# F401.net
KiCad netlist of a schematic drawn in EasyEDA Pro
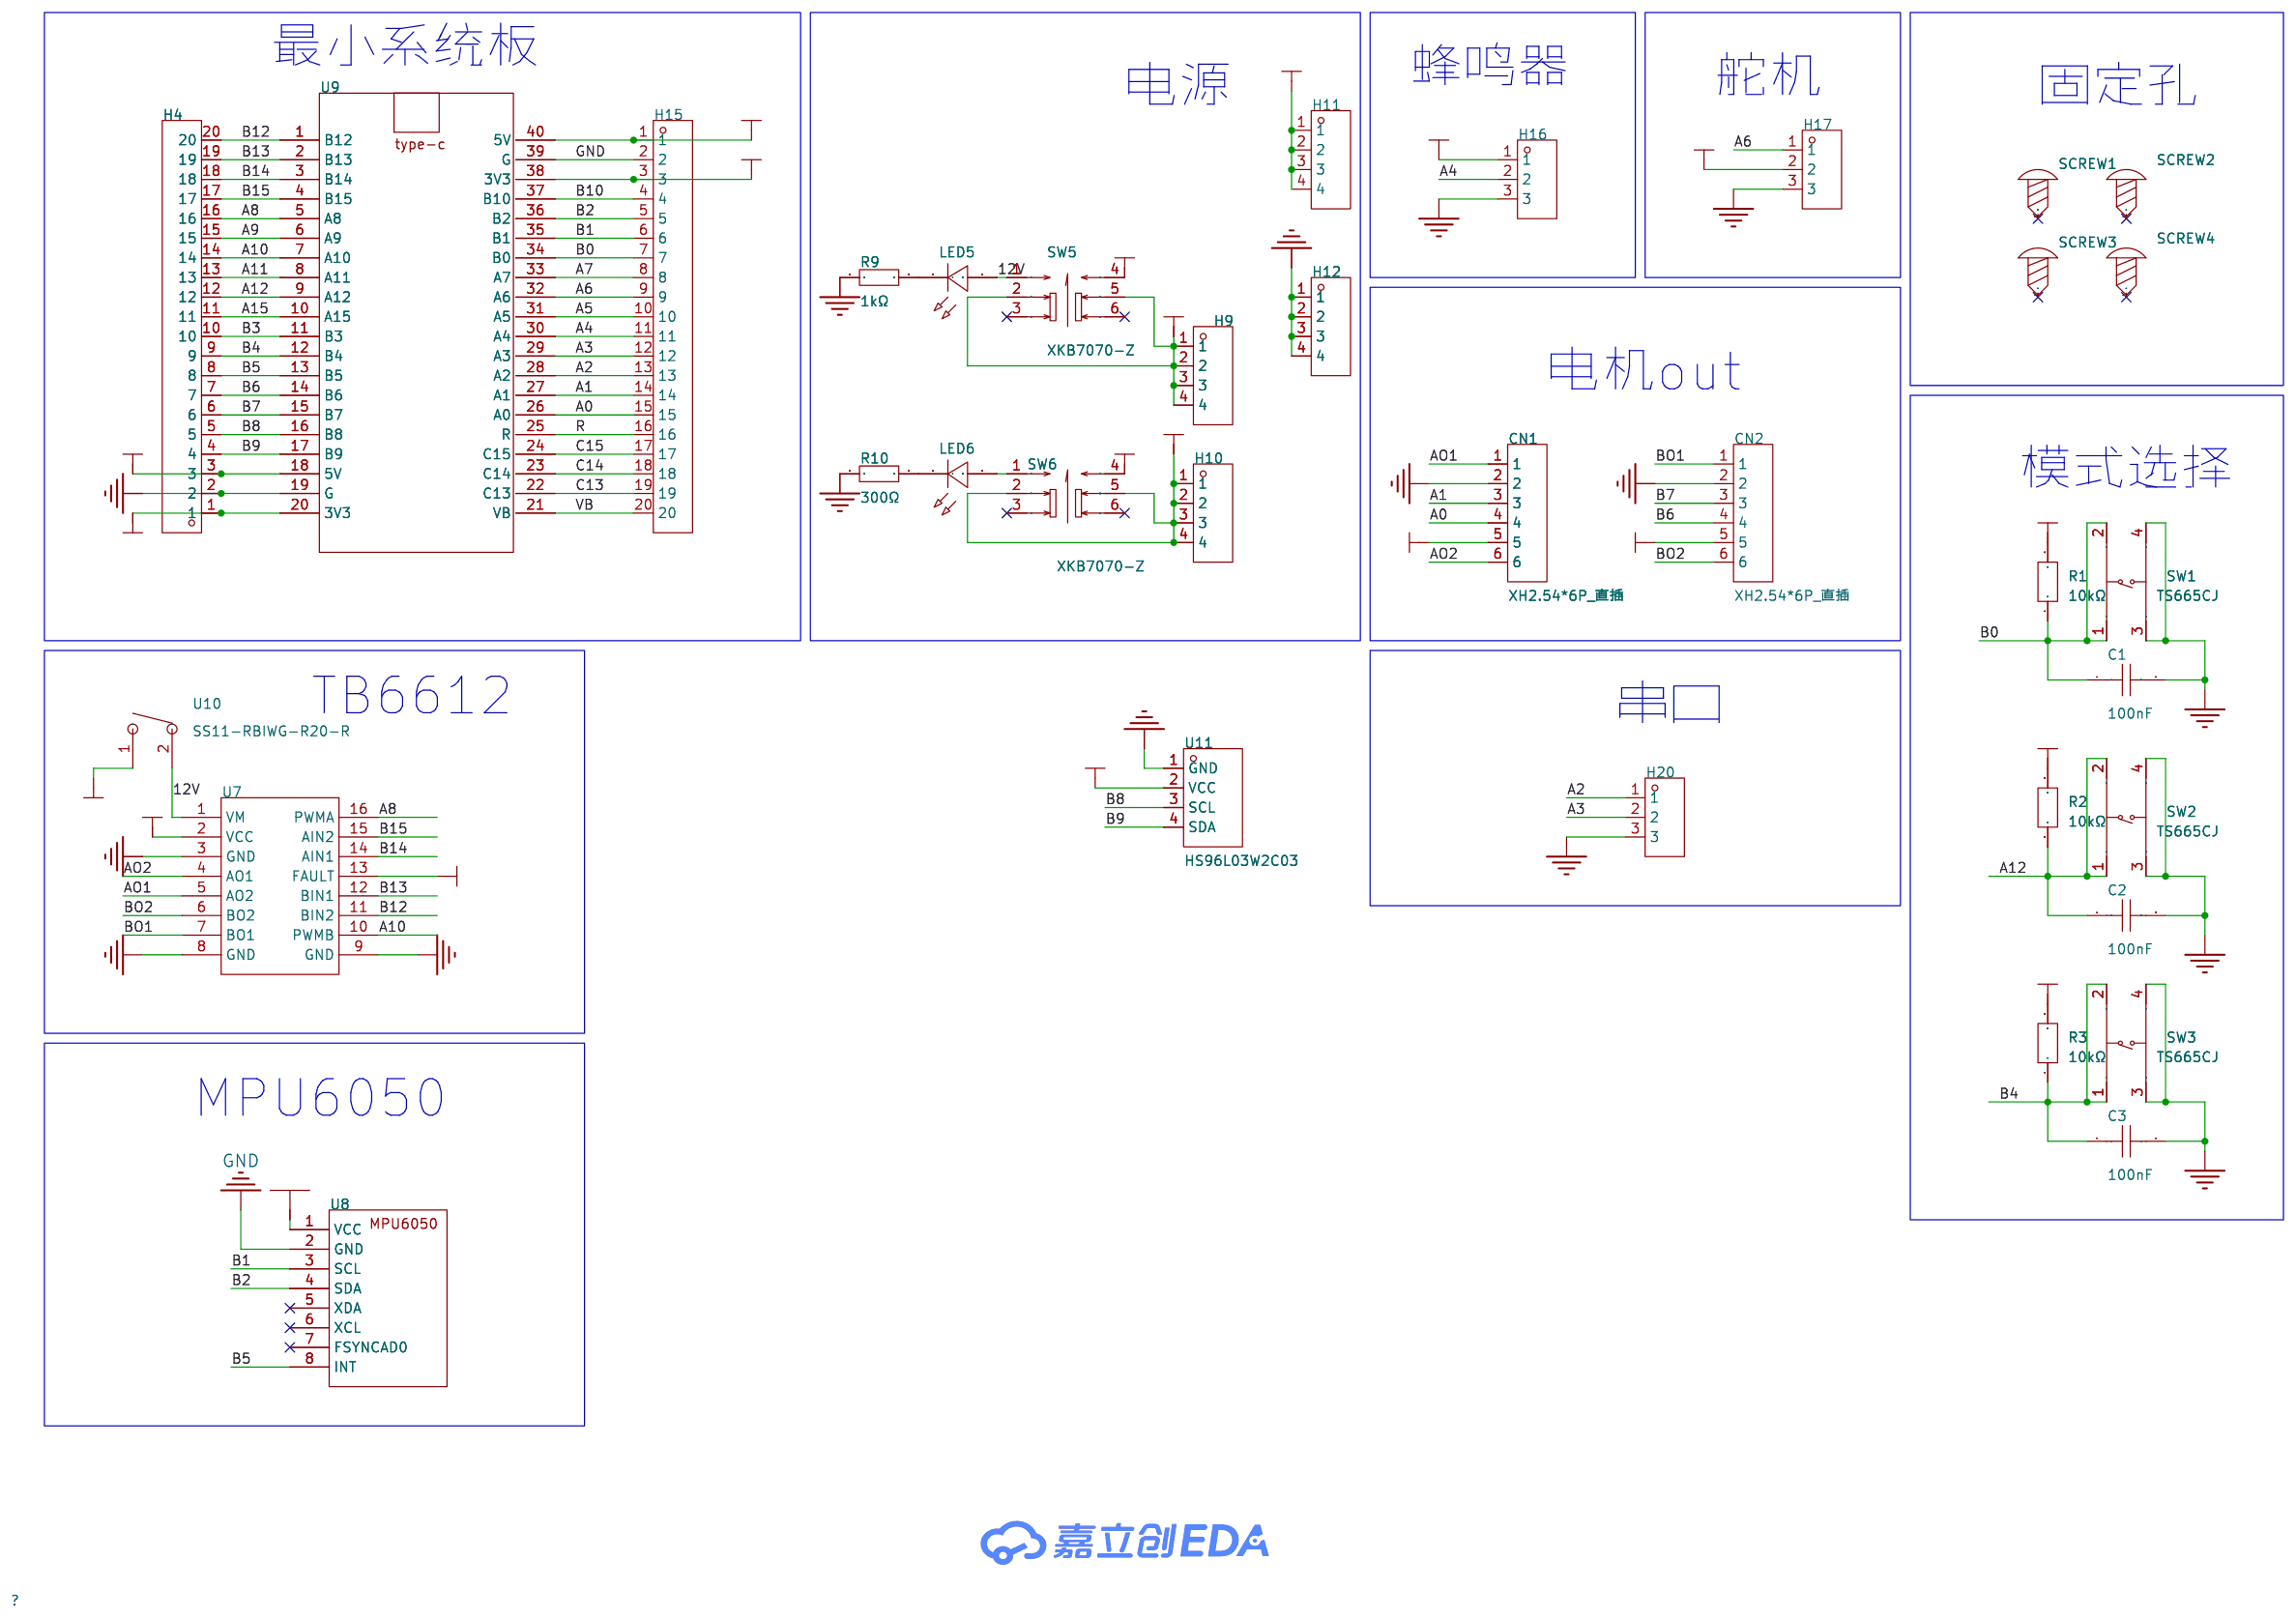
[diagram p0: schematic sheet]

(export (version "E")
  (design (tool "Eeschema 10.0.6"))
  (components
    (comp (ref "C1")
      (value "100nF")
      (footprint "easyedapro:CAP-TH_L5.0-W2.5-P5.00-D1.0")
      (description "容值:100nF;精度:±20%;额定电压:50V;温度系数:Y5V;")
      (fields
        (field (name "Manufacturer Part") "CC1H104MC1FD3F6C10MF")
        (field (name "Manufacturer") "Dersonic(德尔创)")
      )
      (libsource (lib "easyedapro") (part "CC1H104MC1FD3F6C10MF"))
    )
    (comp (ref "C2")
      (value "100nF")
      (footprint "easyedapro:CAP-TH_L5.0-W2.5-P5.00-D1.0")
      (description "容值:100nF;精度:±20%;额定电压:50V;温度系数:Y5V;")
      (fields
        (field (name "Manufacturer Part") "CC1H104MC1FD3F6C10MF")
        (field (name "Manufacturer") "Dersonic(德尔创)")
      )
      (libsource (lib "easyedapro") (part "CC1H104MC1FD3F6C10MF"))
    )
    (comp (ref "C3")
      (value "100nF")
      (footprint "easyedapro:CAP-TH_L5.0-W2.5-P5.00-D1.0")
      (description "容值:100nF;精度:±20%;额定电压:50V;温度系数:Y5V;")
      (fields
        (field (name "Manufacturer Part") "CC1H104MC1FD3F6C10MF")
        (field (name "Manufacturer") "Dersonic(德尔创)")
      )
      (libsource (lib "easyedapro") (part "CC1H104MC1FD3F6C10MF"))
    )
    (comp (ref "CN1")
      (value "XH2.54*6P_直插")
      (footprint "easyedapro:CONN-TH_XH2.54-6P")
      (libsource (lib "easyedapro") (part "XH2.54*6P_直插"))
    )
    (comp (ref "CN2")
      (value "XH2.54*6P_直插")
      (footprint "easyedapro:CONN-TH_XH2.54-6P")
      (libsource (lib "easyedapro") (part "XH2.54*6P_直插"))
    )
    (comp (ref "H4")
      (value "~")
      (footprint "easyedapro:HDR-TH_20P-P2.54-V-M-1")
      (libsource (lib "easyedapro") (part "HDR_2.54-1x20P"))
    )
    (comp (ref "H9")
      (value "~")
      (footprint "easyedapro:HDR-TH_4P-P2.54-V-M")
      (libsource (lib "easyedapro") (part "PZ254V-11-04P"))
    )
    (comp (ref "H10")
      (value "~")
      (footprint "easyedapro:HDR-TH_4P-P2.54-V-M")
      (libsource (lib "easyedapro") (part "PZ254V-11-04P"))
    )
    (comp (ref "H11")
      (value "~")
      (footprint "easyedapro:HDR-TH_4P-P2.54-V-M")
      (libsource (lib "easyedapro") (part "PZ254V-11-04P"))
    )
    (comp (ref "H12")
      (value "~")
      (footprint "easyedapro:HDR-TH_4P-P2.54-V-M")
      (libsource (lib "easyedapro") (part "PZ254V-11-04P"))
    )
    (comp (ref "H15")
      (value "~")
      (footprint "easyedapro:HDR-TH_20P-P2.54-V-M-1")
      (libsource (lib "easyedapro") (part "HDR_2.54-1x20P"))
    )
    (comp (ref "H16")
      (value "~")
      (footprint "easyedapro:HDR-TH_3P-P2.54-V-F")
      (libsource (lib "easyedapro") (part "PM254V-11-03-H85"))
    )
    (comp (ref "H17")
      (value "~")
      (footprint "easyedapro:HDR-TH_3P-P2.54-V-M")
      (libsource (lib "easyedapro") (part "PZ254V-11-03P_C2937625"))
    )
    (comp (ref "H20")
      (value "~")
      (footprint "easyedapro:HDR-TH_3P-P2.54-V-M")
      (libsource (lib "easyedapro") (part "PZ254V-11-03P_C2937625"))
    )
    (comp (ref "LED5")
      (value "~")
      (footprint "easyedapro:LED_TH-3mm")
      (libsource (lib "easyedapro") (part "LED_TH-R"))
    )
    (comp (ref "LED6")
      (value "~")
      (footprint "easyedapro:LED_TH-3mm")
      (libsource (lib "easyedapro") (part "LED_TH-R"))
    )
    (comp (ref "R1")
      (value "10kΩ")
      (footprint "easyedapro:RES-TH_BD2.7-L6.2-P10.20-D0.4")
      (description "电阻类型:金属膜电阻;阻值:1kΩ;精度:±1%;功率:250mW;温度系数:±100ppm/°C;")
      (fields (field (name "Manufacturer Part") "MF1/4W-1K±1%-ST52") (field (name "Manufacturer") "VO(翔胜)"))
      (libsource (lib "easyedapro") (part "MF1/4W-1K±1%-ST52"))
    )
    (comp (ref "R2")
      (value "10kΩ")
      (footprint "easyedapro:RES-TH_BD2.7-L6.2-P10.20-D0.4")
      (description "电阻类型:金属膜电阻;阻值:1kΩ;精度:±1%;功率:250mW;温度系数:±100ppm/°C;")
      (fields (field (name "Manufacturer Part") "MF1/4W-1K±1%-ST52") (field (name "Manufacturer") "VO(翔胜)"))
      (libsource (lib "easyedapro") (part "MF1/4W-1K±1%-ST52"))
    )
    (comp (ref "R3")
      (value "10kΩ")
      (footprint "easyedapro:RES-TH_BD2.7-L6.2-P10.20-D0.4")
      (description "电阻类型:金属膜电阻;阻值:1kΩ;精度:±1%;功率:250mW;温度系数:±100ppm/°C;")
      (fields (field (name "Manufacturer Part") "MF1/4W-1K±1%-ST52") (field (name "Manufacturer") "VO(翔胜)"))
      (libsource (lib "easyedapro") (part "MF1/4W-1K±1%-ST52"))
    )
    (comp (ref "R9")
      (value "1kΩ")
      (footprint "easyedapro:Res_1/2W")
      (libsource (lib "easyedapro") (part "电阻"))
    )
    (comp (ref "R10")
      (value "300Ω")
      (footprint "easyedapro:Res_1/2W")
      (libsource (lib "easyedapro") (part "电阻"))
    )
    (comp (ref "SCREW1")
      (value "~")
      (footprint "easyedapro:M3螺丝")
      (libsource (lib "easyedapro") (part "螺丝孔"))
    )
    (comp (ref "SCREW2")
      (value "~")
      (footprint "easyedapro:M3螺丝")
      (libsource (lib "easyedapro") (part "螺丝孔"))
    )
    (comp (ref "SCREW3")
      (value "~")
      (footprint "easyedapro:M3螺丝")
      (libsource (lib "easyedapro") (part "螺丝孔"))
    )
    (comp (ref "SCREW4")
      (value "~")
      (footprint "easyedapro:M3螺丝")
      (libsource (lib "easyedapro") (part "螺丝孔"))
    )
    (comp (ref "SW1")
      (value "TS665CJ")
      (footprint "easyedapro:SW-TH_4P-L6.0-W6.0-P4.50-LS6.5")
      (description "电路结构:单刀单掷;按钮形状:圆形按钮;安装方式:直插;开关长度:6mm;开关宽度:6mm;开关高度:5mm;触点电流:50mA;额定电压(DC):12V;带灯:-;机械寿命:-;")
      (fields (field (name "Manufacturer") "SHOU HAN(首韩)"))
      (libsource (lib "easyedapro") (part "TS665CJ"))
    )
    (comp (ref "SW2")
      (value "TS665CJ")
      (footprint "easyedapro:SW-TH_4P-L6.0-W6.0-P4.50-LS6.5")
      (description "电路结构:单刀单掷;按钮形状:圆形按钮;安装方式:直插;开关长度:6mm;开关宽度:6mm;开关高度:5mm;触点电流:50mA;额定电压(DC):12V;带灯:-;机械寿命:-;")
      (fields (field (name "Manufacturer") "SHOU HAN(首韩)"))
      (libsource (lib "easyedapro") (part "TS665CJ"))
    )
    (comp (ref "SW3")
      (value "TS665CJ")
      (footprint "easyedapro:SW-TH_4P-L6.0-W6.0-P4.50-LS6.5")
      (description "电路结构:单刀单掷;按钮形状:圆形按钮;安装方式:直插;开关长度:6mm;开关宽度:6mm;开关高度:5mm;触点电流:50mA;额定电压(DC):12V;带灯:-;机械寿命:-;")
      (fields (field (name "Manufacturer") "SHOU HAN(首韩)"))
      (libsource (lib "easyedapro") (part "TS665CJ"))
    )
    (comp (ref "SW5")
      (value "XKB7070-Z")
      (footprint "easyedapro:SW-TH_6P-L7.0-W7.0-P2.00")
      (description "自锁/无锁:自锁;安装方式:直插;触点电流:100mA;额定电压 (AC):250V;额定电压 (DC):30V;带灯:不带;作用力:160gf;机械寿命:10万次;")
      (fields (field (name "Manufacturer") "XKB Connectivity(中国星坤)"))
      (libsource (lib "easyedapro") (part "XKB7070-Z"))
    )
    (comp (ref "SW6")
      (value "XKB7070-Z")
      (footprint "easyedapro:SW-TH_6P-L7.0-W7.0-P2.00")
      (description "自锁/无锁:自锁;安装方式:直插;触点电流:100mA;额定电压 (AC):250V;额定电压 (DC):30V;带灯:不带;作用力:160gf;机械寿命:10万次;")
      (fields (field (name "Manufacturer") "XKB Connectivity(中国星坤)"))
      (libsource (lib "easyedapro") (part "XKB7070-Z"))
    )
    (comp (ref "U7")
      (value "~")
      (footprint "easyedapro:TB6612FNG")
      (libsource (lib "easyedapro") (part "TB6612FNG"))
    )
    (comp (ref "U8")
      (value "~")
      (footprint "easyedapro:MPU6050")
      (libsource (lib "easyedapro") (part "MPU6050"))
    )
    (comp (ref "U9")
      (value "~")
      (footprint "easyedapro:F401CCU6")
      (libsource (lib "easyedapro") (part "F401CCU6"))
    )
    (comp (ref "U10")
      (value "SS11-RBIWG-R20-R")
      (footprint "easyedapro:SW-TH_L21.0-W15.0_SS11-RBIWG-R20-R")
      (description "带灯:无;额定电流:16A;额定电压(AC):250V;电路结构:单刀单掷;机械寿命:1万次;")
      (fields (field (name "Manufacturer") "Legion(六钧)"))
      (libsource (lib "easyedapro") (part "SS11-RBIWG-R20-R"))
    )
    (comp (ref "U11")
      (value "HS96L03W2C03")
      (footprint "easyedapro:OLED-TH_L27.8-W27.2-P2.54_C9900033791")
      (description "主控芯片:SSD1315;接口类型:I2C;尺寸(inch):0.96;像素分辨率:128x64;")
      (fields (field (name "Manufacturer") "HS(汉昇)"))
      (libsource (lib "easyedapro") (part "HS96L03W2C03"))
    )
  )
  (nets
    (net (code "1") (name "/A0") (class "Default")
      (node (ref "CN1") (pin "4") (pinfunction "4_4") (pintype "unspecified"))
      (node (ref "H15") (pin "15") (pinfunction "15_15") (pintype "input"))
      (node (ref "U9") (pin "26") (pinfunction "A0_26") (pintype "input"))
    )
    (net (code "2") (name "/A1") (class "Default")
      (node (ref "CN1") (pin "3") (pinfunction "3_3") (pintype "unspecified"))
      (node (ref "H15") (pin "14") (pinfunction "14_14") (pintype "input"))
      (node (ref "U9") (pin "27") (pinfunction "A1_27") (pintype "input"))
    )
    (net (code "3") (name "/A2") (class "Default")
      (node (ref "H15") (pin "13") (pinfunction "13_13") (pintype "input"))
      (node (ref "H20") (pin "1") (pinfunction "1_1") (pintype "input"))
      (node (ref "U9") (pin "28") (pinfunction "A2_28") (pintype "input"))
    )
    (net (code "4") (name "/A3") (class "Default")
      (node (ref "H15") (pin "12") (pinfunction "12_12") (pintype "input"))
      (node (ref "H20") (pin "2") (pinfunction "2_2") (pintype "input"))
      (node (ref "U9") (pin "29") (pinfunction "A3_29") (pintype "input"))
    )
    (net (code "5") (name "/A4") (class "Default")
      (node (ref "H15") (pin "11") (pinfunction "11_11") (pintype "input"))
      (node (ref "H16") (pin "2") (pinfunction "2_2") (pintype "unspecified"))
      (node (ref "U9") (pin "30") (pinfunction "A4_30") (pintype "input"))
    )
    (net (code "6") (name "/A5") (class "Default")
      (node (ref "H15") (pin "10") (pinfunction "10_10") (pintype "input"))
      (node (ref "U9") (pin "31") (pinfunction "A5_31") (pintype "input"))
    )
    (net (code "7") (name "/A6") (class "Default")
      (node (ref "H15") (pin "9") (pinfunction "9_9") (pintype "input"))
      (node (ref "H17") (pin "1") (pinfunction "1_1") (pintype "input"))
      (node (ref "U9") (pin "32") (pinfunction "A6_32") (pintype "input"))
    )
    (net (code "8") (name "/A7") (class "Default")
      (node (ref "H15") (pin "8") (pinfunction "8_8") (pintype "input"))
      (node (ref "U9") (pin "33") (pinfunction "A7_33") (pintype "input"))
    )
    (net (code "9") (name "/A8") (class "Default")
      (node (ref "H4") (pin "16") (pinfunction "16_16") (pintype "input"))
      (node (ref "U7") (pin "16") (pinfunction "PWMA_16") (pintype "input"))
      (node (ref "U9") (pin "5") (pinfunction "A8_5") (pintype "input"))
    )
    (net (code "10") (name "/A9") (class "Default")
      (node (ref "H4") (pin "15") (pinfunction "15_15") (pintype "input"))
      (node (ref "U9") (pin "6") (pinfunction "A9_6") (pintype "input"))
    )
    (net (code "11") (name "/A10") (class "Default")
      (node (ref "H4") (pin "14") (pinfunction "14_14") (pintype "input"))
      (node (ref "U7") (pin "10") (pinfunction "PWMB_10") (pintype "input"))
      (node (ref "U9") (pin "7") (pinfunction "A10_7") (pintype "input"))
    )
    (net (code "12") (name "/A11") (class "Default")
      (node (ref "H4") (pin "13") (pinfunction "13_13") (pintype "input"))
      (node (ref "U9") (pin "8") (pinfunction "A11_8") (pintype "input"))
    )
    (net (code "13") (name "/A12") (class "Default")
      (node (ref "C2") (pin "1") (pinfunction "1_1") (pintype "unspecified"))
      (node (ref "H4") (pin "12") (pinfunction "12_12") (pintype "input"))
      (node (ref "R2") (pin "1") (pinfunction "1_1") (pintype "unspecified"))
      (node (ref "SW2") (pin "1") (pinfunction "A_1") (pintype "unspecified"))
      (node (ref "SW2") (pin "2") (pinfunction "B_2") (pintype "unspecified"))
      (node (ref "U9") (pin "9") (pinfunction "A12_9") (pintype "input"))
    )
    (net (code "14") (name "/A15") (class "Default")
      (node (ref "H4") (pin "11") (pinfunction "11_11") (pintype "input"))
      (node (ref "U9") (pin "10") (pinfunction "A15_10") (pintype "input"))
    )
    (net (code "15") (name "/AO1") (class "Default")
      (node (ref "CN1") (pin "1") (pinfunction "1_1") (pintype "unspecified"))
      (node (ref "U7") (pin "5") (pinfunction "AO2_5") (pintype "input"))
    )
    (net (code "16") (name "/AO2") (class "Default")
      (node (ref "CN1") (pin "6") (pinfunction "6_6") (pintype "unspecified"))
      (node (ref "U7") (pin "4") (pinfunction "AO1_4") (pintype "input"))
    )
    (net (code "17") (name "/B0") (class "Default")
      (node (ref "C1") (pin "1") (pinfunction "1_1") (pintype "unspecified"))
      (node (ref "H15") (pin "7") (pinfunction "7_7") (pintype "input"))
      (node (ref "R1") (pin "1") (pinfunction "1_1") (pintype "unspecified"))
      (node (ref "SW1") (pin "1") (pinfunction "A_1") (pintype "unspecified"))
      (node (ref "SW1") (pin "2") (pinfunction "B_2") (pintype "unspecified"))
      (node (ref "U9") (pin "34") (pinfunction "B0_34") (pintype "input"))
    )
    (net (code "18") (name "/B1") (class "Default")
      (node (ref "H15") (pin "6") (pinfunction "6_6") (pintype "input"))
      (node (ref "U8") (pin "3") (pinfunction "SCL_3") (pintype "input"))
      (node (ref "U9") (pin "35") (pinfunction "B1_35") (pintype "input"))
    )
    (net (code "19") (name "/B2") (class "Default")
      (node (ref "H15") (pin "5") (pinfunction "5_5") (pintype "input"))
      (node (ref "U8") (pin "4") (pinfunction "SDA_4") (pintype "input"))
      (node (ref "U9") (pin "36") (pinfunction "B2_36") (pintype "input"))
    )
    (net (code "20") (name "/B3") (class "Default")
      (node (ref "H4") (pin "10") (pinfunction "10_10") (pintype "input"))
      (node (ref "U9") (pin "11") (pinfunction "B3_11") (pintype "input"))
    )
    (net (code "21") (name "/B4") (class "Default")
      (node (ref "C3") (pin "1") (pinfunction "1_1") (pintype "unspecified"))
      (node (ref "H4") (pin "9") (pinfunction "9_9") (pintype "input"))
      (node (ref "R3") (pin "1") (pinfunction "1_1") (pintype "unspecified"))
      (node (ref "SW3") (pin "1") (pinfunction "A_1") (pintype "unspecified"))
      (node (ref "SW3") (pin "2") (pinfunction "B_2") (pintype "unspecified"))
      (node (ref "U9") (pin "12") (pinfunction "B4_12") (pintype "input"))
    )
    (net (code "22") (name "/B5") (class "Default")
      (node (ref "H4") (pin "8") (pinfunction "8_8") (pintype "input"))
      (node (ref "U8") (pin "8") (pinfunction "INT_8") (pintype "input"))
      (node (ref "U9") (pin "13") (pinfunction "B5_13") (pintype "input"))
    )
    (net (code "23") (name "/B6") (class "Default")
      (node (ref "CN2") (pin "4") (pinfunction "4_4") (pintype "unspecified"))
      (node (ref "H4") (pin "7") (pinfunction "7_7") (pintype "input"))
      (node (ref "U9") (pin "14") (pinfunction "B6_14") (pintype "input"))
    )
    (net (code "24") (name "/B7") (class "Default")
      (node (ref "CN2") (pin "3") (pinfunction "3_3") (pintype "unspecified"))
      (node (ref "H4") (pin "6") (pinfunction "6_6") (pintype "input"))
      (node (ref "U9") (pin "15") (pinfunction "B7_15") (pintype "input"))
    )
    (net (code "25") (name "/B8") (class "Default")
      (node (ref "H4") (pin "5") (pinfunction "5_5") (pintype "input"))
      (node (ref "U11") (pin "3") (pinfunction "SCL_3") (pintype "unspecified"))
      (node (ref "U9") (pin "16") (pinfunction "B8_16") (pintype "input"))
    )
    (net (code "26") (name "/B9") (class "Default")
      (node (ref "H4") (pin "4") (pinfunction "4_4") (pintype "input"))
      (node (ref "U11") (pin "4") (pinfunction "SDA_4") (pintype "unspecified"))
      (node (ref "U9") (pin "17") (pinfunction "B9_17") (pintype "input"))
    )
    (net (code "27") (name "/B10") (class "Default")
      (node (ref "H15") (pin "4") (pinfunction "4_4") (pintype "input"))
      (node (ref "U9") (pin "37") (pinfunction "B10_37") (pintype "input"))
    )
    (net (code "28") (name "/B12") (class "Default")
      (node (ref "H4") (pin "20") (pinfunction "20_20") (pintype "input"))
      (node (ref "U7") (pin "11") (pinfunction "BIN2_11") (pintype "input"))
      (node (ref "U9") (pin "1") (pinfunction "B12_1") (pintype "input"))
    )
    (net (code "29") (name "/B13") (class "Default")
      (node (ref "H4") (pin "19") (pinfunction "19_19") (pintype "input"))
      (node (ref "U7") (pin "12") (pinfunction "BIN1_12") (pintype "input"))
      (node (ref "U9") (pin "2") (pinfunction "B13_2") (pintype "input"))
    )
    (net (code "30") (name "/B14") (class "Default")
      (node (ref "H4") (pin "18") (pinfunction "18_18") (pintype "input"))
      (node (ref "U7") (pin "14") (pinfunction "AIN1_14") (pintype "input"))
      (node (ref "U9") (pin "3") (pinfunction "B14_3") (pintype "input"))
    )
    (net (code "31") (name "/B15") (class "Default")
      (node (ref "H4") (pin "17") (pinfunction "17_17") (pintype "input"))
      (node (ref "U7") (pin "15") (pinfunction "AIN2_15") (pintype "input"))
      (node (ref "U9") (pin "4") (pinfunction "B15_4") (pintype "input"))
    )
    (net (code "32") (name "/BO1") (class "Default")
      (node (ref "CN2") (pin "1") (pinfunction "1_1") (pintype "unspecified"))
      (node (ref "U7") (pin "7") (pinfunction "BO1_7") (pintype "input"))
    )
    (net (code "33") (name "/BO2") (class "Default")
      (node (ref "CN2") (pin "6") (pinfunction "6_6") (pintype "unspecified"))
      (node (ref "U7") (pin "6") (pinfunction "BO2_6") (pintype "input"))
    )
    (net (code "34") (name "/C13") (class "Default")
      (node (ref "H15") (pin "19") (pinfunction "19_19") (pintype "input"))
      (node (ref "U9") (pin "22") (pinfunction "C13_22") (pintype "input"))
    )
    (net (code "35") (name "/C14") (class "Default")
      (node (ref "H15") (pin "18") (pinfunction "18_18") (pintype "input"))
      (node (ref "U9") (pin "23") (pinfunction "C14_23") (pintype "input"))
    )
    (net (code "36") (name "/C15") (class "Default")
      (node (ref "H15") (pin "17") (pinfunction "17_17") (pintype "input"))
      (node (ref "U9") (pin "24") (pinfunction "C15_24") (pintype "input"))
    )
    (net (code "37") (name "/R") (class "Default")
      (node (ref "H15") (pin "16") (pinfunction "16_16") (pintype "input"))
      (node (ref "U9") (pin "25") (pinfunction "R_25") (pintype "input"))
    )
    (net (code "38") (name "/VB") (class "Default")
      (node (ref "H15") (pin "20") (pinfunction "20_20") (pintype "input"))
      (node (ref "U9") (pin "21") (pinfunction "VB_21") (pintype "input"))
    )
    (net (code "39") (name "3V3") (class "Default")
      (node (ref "H11") (pin "1") (pinfunction "1_1") (pintype "unspecified"))
      (node (ref "H11") (pin "2") (pinfunction "2_2") (pintype "unspecified"))
      (node (ref "H11") (pin "3") (pinfunction "3_3") (pintype "unspecified"))
      (node (ref "H11") (pin "4") (pinfunction "4_4") (pintype "unspecified"))
      (node (ref "H15") (pin "3") (pinfunction "3_3") (pintype "input"))
      (node (ref "H16") (pin "1") (pinfunction "1_1") (pintype "unspecified"))
      (node (ref "H4") (pin "1") (pinfunction "1_1") (pintype "input"))
      (node (ref "R1") (pin "2") (pinfunction "2_2") (pintype "unspecified"))
      (node (ref "R2") (pin "2") (pinfunction "2_2") (pintype "unspecified"))
      (node (ref "R3") (pin "2") (pinfunction "2_2") (pintype "unspecified"))
      (node (ref "U11") (pin "2") (pinfunction "VCC_2") (pintype "unspecified"))
      (node (ref "U9") (pin "20") (pinfunction "3V3_20") (pintype "input"))
      (node (ref "U9") (pin "38") (pinfunction "3V3_38") (pintype "input"))
    )
    (net (code "40") (name "5V") (class "Default")
      (node (ref "CN1") (pin "5") (pinfunction "5_5") (pintype "unspecified"))
      (node (ref "CN2") (pin "5") (pinfunction "5_5") (pintype "unspecified"))
      (node (ref "H10") (pin "1") (pinfunction "1_1") (pintype "unspecified"))
      (node (ref "H10") (pin "2") (pinfunction "2_2") (pintype "unspecified"))
      (node (ref "H10") (pin "3") (pinfunction "3_3") (pintype "unspecified"))
      (node (ref "H10") (pin "4") (pinfunction "4_4") (pintype "unspecified"))
      (node (ref "H15") (pin "1") (pinfunction "1_1") (pintype "input"))
      (node (ref "H17") (pin "2") (pinfunction "2_2") (pintype "input"))
      (node (ref "H4") (pin "3") (pinfunction "3_3") (pintype "input"))
      (node (ref "SW6") (pin "2") (pinfunction "2_2") (pintype "unspecified"))
      (node (ref "SW6") (pin "4") (pinfunction "4_4") (pintype "unspecified"))
      (node (ref "SW6") (pin "5") (pinfunction "5_5") (pintype "unspecified"))
      (node (ref "U7") (pin "13") (pinfunction "FAULT_13") (pintype "input"))
      (node (ref "U7") (pin "2") (pinfunction "VCC_2") (pintype "input"))
      (node (ref "U8") (pin "1") (pinfunction "VCC_1") (pintype "input"))
      (node (ref "U9") (pin "18") (pinfunction "5V_18") (pintype "input"))
      (node (ref "U9") (pin "40") (pinfunction "5V_40") (pintype "input"))
    )
    (net (code "41") (name "12V") (class "Default")
      (node (ref "H9") (pin "1") (pinfunction "1_1") (pintype "unspecified"))
      (node (ref "H9") (pin "2") (pinfunction "2_2") (pintype "unspecified"))
      (node (ref "H9") (pin "3") (pinfunction "3_3") (pintype "unspecified"))
      (node (ref "H9") (pin "4") (pinfunction "4_4") (pintype "unspecified"))
      (node (ref "LED5") (pin "1") (pinfunction "C_1") (pintype "input"))
      (node (ref "SW5") (pin "1") (pinfunction "1_1") (pintype "unspecified"))
      (node (ref "SW5") (pin "2") (pinfunction "2_2") (pintype "unspecified"))
      (node (ref "SW5") (pin "4") (pinfunction "4_4") (pintype "unspecified"))
      (node (ref "SW5") (pin "5") (pinfunction "5_5") (pintype "unspecified"))
      (node (ref "U10") (pin "1") (pinfunction "1_1") (pintype "unspecified"))
      (node (ref "U10") (pin "2") (pinfunction "2_2") (pintype "unspecified"))
      (node (ref "U7") (pin "1") (pinfunction "VM_1") (pintype "input"))
    )
    (net (code "42") (name "GND") (class "Default")
      (node (ref "C1") (pin "2") (pinfunction "2_2") (pintype "unspecified"))
      (node (ref "C2") (pin "2") (pinfunction "2_2") (pintype "unspecified"))
      (node (ref "C3") (pin "2") (pinfunction "2_2") (pintype "unspecified"))
      (node (ref "CN1") (pin "2") (pinfunction "2_2") (pintype "unspecified"))
      (node (ref "CN2") (pin "2") (pinfunction "2_2") (pintype "unspecified"))
      (node (ref "H12") (pin "1") (pinfunction "1_1") (pintype "unspecified"))
      (node (ref "H12") (pin "2") (pinfunction "2_2") (pintype "unspecified"))
      (node (ref "H12") (pin "3") (pinfunction "3_3") (pintype "unspecified"))
      (node (ref "H12") (pin "4") (pinfunction "4_4") (pintype "unspecified"))
      (node (ref "H15") (pin "2") (pinfunction "2_2") (pintype "input"))
      (node (ref "H16") (pin "3") (pinfunction "3_3") (pintype "unspecified"))
      (node (ref "H17") (pin "3") (pinfunction "3_3") (pintype "input"))
      (node (ref "H20") (pin "3") (pinfunction "3_3") (pintype "input"))
      (node (ref "H4") (pin "2") (pinfunction "2_2") (pintype "input"))
      (node (ref "R10") (pin "1") (pinfunction "1_1") (pintype "input"))
      (node (ref "R9") (pin "1") (pinfunction "1_1") (pintype "input"))
      (node (ref "SW1") (pin "3") (pinfunction "C_3") (pintype "unspecified"))
      (node (ref "SW1") (pin "4") (pinfunction "D_4") (pintype "unspecified"))
      (node (ref "SW2") (pin "3") (pinfunction "C_3") (pintype "unspecified"))
      (node (ref "SW2") (pin "4") (pinfunction "D_4") (pintype "unspecified"))
      (node (ref "SW3") (pin "3") (pinfunction "C_3") (pintype "unspecified"))
      (node (ref "SW3") (pin "4") (pinfunction "D_4") (pintype "unspecified"))
      (node (ref "U11") (pin "1") (pinfunction "GND_1") (pintype "unspecified"))
      (node (ref "U7") (pin "3") (pinfunction "GND_3") (pintype "input"))
      (node (ref "U7") (pin "8") (pinfunction "GND_8") (pintype "input"))
      (node (ref "U7") (pin "9") (pinfunction "GND_9") (pintype "input"))
      (node (ref "U8") (pin "2") (pinfunction "GND_2") (pintype "input"))
      (node (ref "U9") (pin "19") (pinfunction "G_19") (pintype "input"))
      (node (ref "U9") (pin "39") (pinfunction "G_39") (pintype "input"))
    )
    (net (code "43") (name "Net-(LED5-A)") (class "Default")
      (node (ref "LED5") (pin "2") (pinfunction "A_2") (pintype "input"))
      (node (ref "R9") (pin "2") (pinfunction "2_2") (pintype "input"))
    )
    (net (code "44") (name "Net-(LED6-A)") (class "Default")
      (node (ref "LED6") (pin "2") (pinfunction "A_2") (pintype "input"))
      (node (ref "R10") (pin "2") (pinfunction "2_2") (pintype "input"))
    )
    (net (code "45") (name "Net-(LED6-C)") (class "Default")
      (node (ref "LED6") (pin "1") (pinfunction "C_1") (pintype "input"))
      (node (ref "SW6") (pin "1") (pinfunction "1_1") (pintype "unspecified"))
    )
    (net (code "46") (name "unconnected-(SCREW1-Pad1)") (class "Default")
      (node (ref "SCREW1") (pin "1") (pinfunction "1_1") (pintype "input+no_connect"))
    )
    (net (code "47") (name "unconnected-(SCREW2-Pad1)") (class "Default")
      (node (ref "SCREW2") (pin "1") (pinfunction "1_1") (pintype "input+no_connect"))
    )
    (net (code "48") (name "unconnected-(SCREW3-Pad1)") (class "Default")
      (node (ref "SCREW3") (pin "1") (pinfunction "1_1") (pintype "input+no_connect"))
    )
    (net (code "49") (name "unconnected-(SCREW4-Pad1)") (class "Default")
      (node (ref "SCREW4") (pin "1") (pinfunction "1_1") (pintype "input+no_connect"))
    )
    (net (code "50") (name "unconnected-(SW5-Pad3)") (class "Default")
      (node (ref "SW5") (pin "3") (pinfunction "3_3") (pintype "unspecified+no_connect"))
    )
    (net (code "51") (name "unconnected-(SW5-Pad6)") (class "Default")
      (node (ref "SW5") (pin "6") (pinfunction "6_6") (pintype "unspecified+no_connect"))
    )
    (net (code "52") (name "unconnected-(SW6-Pad3)") (class "Default")
      (node (ref "SW6") (pin "3") (pinfunction "3_3") (pintype "unspecified+no_connect"))
    )
    (net (code "53") (name "unconnected-(SW6-Pad6)") (class "Default")
      (node (ref "SW6") (pin "6") (pinfunction "6_6") (pintype "unspecified+no_connect"))
    )
    (net (code "54") (name "unconnected-(U8-FSYNCAD0-Pad7)") (class "Default")
      (node (ref "U8") (pin "7") (pinfunction "FSYNCAD0_7") (pintype "input+no_connect"))
    )
    (net (code "55") (name "unconnected-(U8-XCL-Pad6)") (class "Default")
      (node (ref "U8") (pin "6") (pinfunction "XCL_6") (pintype "input+no_connect"))
    )
    (net (code "56") (name "unconnected-(U8-XDA-Pad5)") (class "Default")
      (node (ref "U8") (pin "5") (pinfunction "XDA_5") (pintype "input+no_connect"))
    )
  )
)
